# haystack_opto.net
KiCad netlist of a schematic drawn in EAGLE
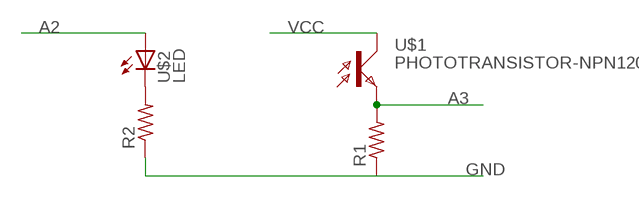
[diagram p0: schematic, sheet 1]

(export (version "E")
  (design (tool "Eeschema 10.0.6"))
  (components
    (comp (ref "R1")
      (value "RES-US1206")
      (footprint "eagle-import:R1206")
      (libsource (lib "eagle-import") (part "RES-US1206"))
    )
    (comp (ref "R2")
      (value "RES-US1206")
      (footprint "eagle-import:R1206")
      (libsource (lib "eagle-import") (part "RES-US1206"))
    )
    (comp (ref "U$1")
      (value "PHOTOTRANSISTOR-NPN1206")
      (footprint "eagle-import:OP1206")
      (libsource (lib "eagle-import") (part "PHOTOTRANSISTOR-NPN1206"))
    )
    (comp (ref "U$2")
      (value "LED")
      (footprint "eagle-import:LED1206")
      (libsource (lib "eagle-import") (part "LED"))
    )
  )
  (nets
    (net (code "1") (name "/A2") (class "Default")
      (node (ref "U$2") (pin "1") (pinfunction "A_1") (pintype "passive"))
    )
    (net (code "2") (name "/A3") (class "Default")
      (node (ref "R1") (pin "2") (pinfunction "2_2") (pintype "passive"))
      (node (ref "U$1") (pin "EMITTER") (pinfunction "E_EMITTER") (pintype "passive"))
    )
    (net (code "3") (name "/GND") (class "Default")
      (node (ref "R1") (pin "1") (pinfunction "1_1") (pintype "passive"))
      (node (ref "R2") (pin "1") (pinfunction "1_1") (pintype "passive"))
    )
    (net (code "4") (name "/VCC") (class "Default")
      (node (ref "U$1") (pin "COLLECTOR") (pinfunction "C_COLLECTOR") (pintype "passive"))
    )
    (net (code "5") (name "Net-(U$2-C)") (class "Default")
      (node (ref "R2") (pin "2") (pinfunction "2_2") (pintype "passive"))
      (node (ref "U$2") (pin "2") (pinfunction "C_2") (pintype "passive"))
    )
  )
)
